# tap_sens.net
KiCad netlist of a schematic drawn in EAGLE
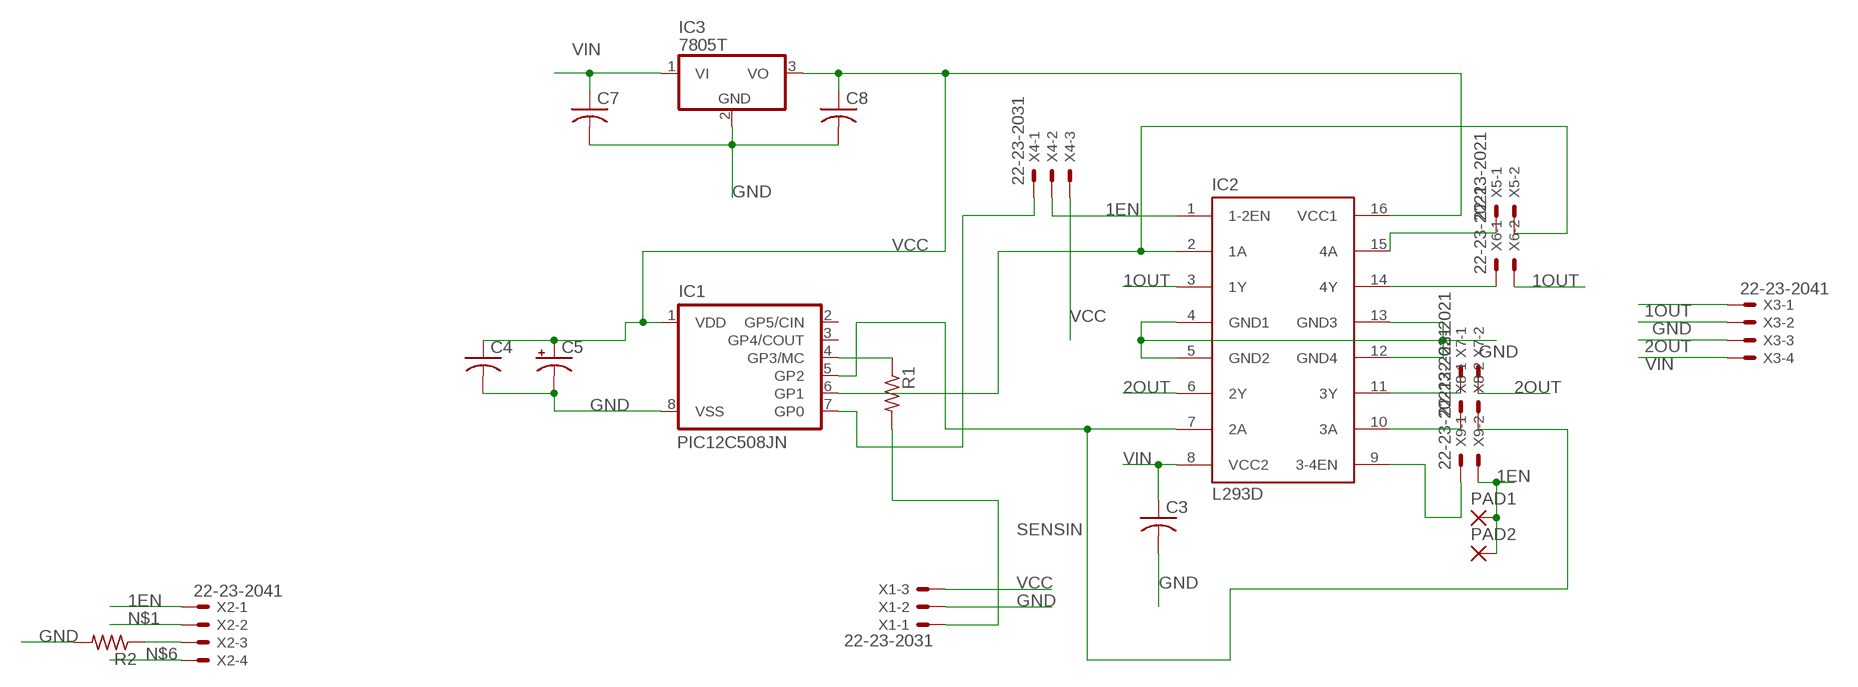
[diagram p0: schematic, sheet 1]

(export (version "E")
  (design (tool "Eeschema 10.0.6"))
  (components
    (comp (ref "C3")
      (value "C-US050-025X075")
      (footprint "eagle-import:C050-025X075")
      (libsource (lib "eagle-import") (part "C-US050-025X075"))
    )
    (comp (ref "C4")
      (value "C-US050-025X075")
      (footprint "eagle-import:C050-025X075")
      (libsource (lib "eagle-import") (part "C-US050-025X075"))
    )
    (comp (ref "C5")
      (value "CPOL-USE5-8.5")
      (footprint "eagle-import:E5-8,5")
      (libsource (lib "eagle-import") (part "CPOL-USE5-8.5"))
    )
    (comp (ref "C7")
      (value "C-US050-025X075")
      (footprint "eagle-import:C050-025X075")
      (libsource (lib "eagle-import") (part "C-US050-025X075"))
    )
    (comp (ref "C8")
      (value "C-US050-025X075")
      (footprint "eagle-import:C050-025X075")
      (libsource (lib "eagle-import") (part "C-US050-025X075"))
    )
    (comp (ref "IC1")
      (value "PIC12C508JN")
      (footprint "eagle-import:DIL8")
      (fields (field (name "MF") "MICROCHIP") (field (name "MPN") "PIC12C508-04/P"))
      (libsource (lib "eagle-import") (part "PIC12C?JN508"))
    )
    (comp (ref "IC2")
      (value "L293D")
      (footprint "eagle-import:DIL16")
      (libsource (lib "eagle-import") (part "L293D"))
    )
    (comp (ref "IC3")
      (value "7805T")
      (footprint "eagle-import:TO220H")
      (libsource (lib "eagle-import") (part "78T05"))
    )
    (comp (ref "PAD1")
      (value "2,54/0,8")
      (footprint "eagle-import:2,54_0,8")
      (libsource (lib "eagle-import") (part "2,54/0,8"))
    )
    (comp (ref "PAD2")
      (value "2,54/0,8")
      (footprint "eagle-import:2,54_0,8")
      (libsource (lib "eagle-import") (part "2,54/0,8"))
    )
    (comp (ref "R1")
      (value "R-US_0207/10")
      (footprint "eagle-import:0207_10")
      (libsource (lib "eagle-import") (part "R-US_0207/10"))
    )
    (comp (ref "R2")
      (value "R-US_0207/10")
      (footprint "eagle-import:0207_10")
      (libsource (lib "eagle-import") (part "R-US_0207/10"))
    )
    (comp (ref "X1")
      (value "22-23-2031")
      (footprint "eagle-import:22-23-2031")
      (fields (field (name "MF") "MOLEX"))
      (libsource (lib "eagle-import") (part "22-23-2031"))
    )
    (comp (ref "X2")
      (value "22-23-2041")
      (footprint "eagle-import:22-23-2041")
      (fields (field (name "MF") "MOLEX"))
      (libsource (lib "eagle-import") (part "22-23-2041"))
    )
    (comp (ref "X3")
      (value "22-23-2041")
      (footprint "eagle-import:22-23-2041")
      (fields (field (name "MF") "MOLEX"))
      (libsource (lib "eagle-import") (part "22-23-2041"))
    )
    (comp (ref "X4")
      (value "22-23-2031")
      (footprint "eagle-import:22-23-2031")
      (fields (field (name "MF") "MOLEX"))
      (libsource (lib "eagle-import") (part "22-23-2031"))
    )
    (comp (ref "X5")
      (value "22-23-2021")
      (footprint "eagle-import:22-23-2021")
      (fields (field (name "MF") "MOLEX"))
      (libsource (lib "eagle-import") (part "22-23-2021"))
    )
    (comp (ref "X6")
      (value "22-23-2021")
      (footprint "eagle-import:22-23-2021")
      (fields (field (name "MF") "MOLEX"))
      (libsource (lib "eagle-import") (part "22-23-2021"))
    )
    (comp (ref "X7")
      (value "22-23-2021")
      (footprint "eagle-import:22-23-2021")
      (fields (field (name "MF") "MOLEX"))
      (libsource (lib "eagle-import") (part "22-23-2021"))
    )
    (comp (ref "X8")
      (value "22-23-2021")
      (footprint "eagle-import:22-23-2021")
      (fields (field (name "MF") "MOLEX"))
      (libsource (lib "eagle-import") (part "22-23-2021"))
    )
    (comp (ref "X9")
      (value "22-23-2021")
      (footprint "eagle-import:22-23-2021")
      (fields (field (name "MF") "MOLEX"))
      (libsource (lib "eagle-import") (part "22-23-2021"))
    )
  )
  (nets
    (net (code "1") (name "/1EN") (class "Default")
      (node (ref "IC2") (pin "1") (pinfunction "1-2EN_1") (pintype "input"))
      (node (ref "PAD1") (pin "1") (pinfunction "P_1") (pintype "passive"))
      (node (ref "PAD2") (pin "1") (pinfunction "P_1") (pintype "passive"))
      (node (ref "X2") (pin "1") (pinfunction "S_1") (pintype "passive"))
      (node (ref "X4") (pin "2") (pinfunction "S_2") (pintype "passive"))
      (node (ref "X9") (pin "2") (pinfunction "S_2") (pintype "passive"))
    )
    (net (code "2") (name "/1OUT") (class "Default")
      (node (ref "IC2") (pin "3") (pinfunction "1Y_3") (pintype "output"))
      (node (ref "X3") (pin "1") (pinfunction "S_1") (pintype "passive"))
      (node (ref "X6") (pin "2") (pinfunction "S_2") (pintype "passive"))
    )
    (net (code "3") (name "/2OUT") (class "Default")
      (node (ref "IC2") (pin "6") (pinfunction "2Y_6") (pintype "output"))
      (node (ref "X3") (pin "3") (pinfunction "S_3") (pintype "passive"))
      (node (ref "X7") (pin "2") (pinfunction "S_2") (pintype "passive"))
    )
    (net (code "4") (name "/GND") (class "Default")
      (node (ref "C3") (pin "2") (pinfunction "2_2") (pintype "passive"))
      (node (ref "C4") (pin "2") (pinfunction "2_2") (pintype "passive"))
      (node (ref "C5") (pin "-") (pinfunction "-_-") (pintype "passive"))
      (node (ref "C7") (pin "2") (pinfunction "2_2") (pintype "passive"))
      (node (ref "C8") (pin "2") (pinfunction "2_2") (pintype "passive"))
      (node (ref "IC1") (pin "8") (pinfunction "VSS_8") (pintype "power_in"))
      (node (ref "IC2") (pin "12") (pinfunction "GND4_12") (pintype "power_in"))
      (node (ref "IC2") (pin "13") (pinfunction "GND3_13") (pintype "power_in"))
      (node (ref "IC2") (pin "4") (pinfunction "GND1_4") (pintype "power_in"))
      (node (ref "IC2") (pin "5") (pinfunction "GND2_5") (pintype "power_in"))
      (node (ref "IC3") (pin "2") (pinfunction "GND_2") (pintype "passive"))
      (node (ref "R2") (pin "2") (pinfunction "2_2") (pintype "passive"))
      (node (ref "X1") (pin "2") (pinfunction "S_2") (pintype "passive"))
      (node (ref "X3") (pin "2") (pinfunction "S_2") (pintype "passive"))
    )
    (net (code "5") (name "/N$1") (class "Default")
      (node (ref "IC1") (pin "6") (pinfunction "GP1_6") (pintype "bidirectional"))
      (node (ref "IC2") (pin "2") (pinfunction "1A_2") (pintype "input"))
      (node (ref "X2") (pin "2") (pinfunction "S_2") (pintype "passive"))
      (node (ref "X5") (pin "2") (pinfunction "S_2") (pintype "passive"))
    )
    (net (code "6") (name "/N$6") (class "Default")
      (node (ref "IC1") (pin "5") (pinfunction "GP2_5") (pintype "bidirectional"))
      (node (ref "IC2") (pin "7") (pinfunction "2A_7") (pintype "input"))
      (node (ref "X2") (pin "4") (pinfunction "S_4") (pintype "passive"))
      (node (ref "X8") (pin "2") (pinfunction "S_2") (pintype "passive"))
    )
    (net (code "7") (name "/SENSIN") (class "Default")
      (node (ref "R1") (pin "2") (pinfunction "2_2") (pintype "passive"))
      (node (ref "X1") (pin "1") (pinfunction "S_1") (pintype "passive"))
    )
    (net (code "8") (name "/VCC") (class "Default")
      (node (ref "C4") (pin "1") (pinfunction "1_1") (pintype "passive"))
      (node (ref "C5") (pin "+") (pinfunction "+_+") (pintype "passive"))
      (node (ref "C8") (pin "1") (pinfunction "1_1") (pintype "passive"))
      (node (ref "IC1") (pin "1") (pinfunction "VDD_1") (pintype "power_in"))
      (node (ref "IC2") (pin "16") (pinfunction "VCC1_16") (pintype "power_in"))
      (node (ref "IC3") (pin "3") (pinfunction "VO_3") (pintype "passive"))
      (node (ref "X1") (pin "3") (pinfunction "S_3") (pintype "passive"))
      (node (ref "X4") (pin "3") (pinfunction "S_3") (pintype "passive"))
    )
    (net (code "9") (name "/VIN") (class "Default")
      (node (ref "C3") (pin "1") (pinfunction "1_1") (pintype "passive"))
      (node (ref "C7") (pin "1") (pinfunction "1_1") (pintype "passive"))
      (node (ref "IC2") (pin "8") (pinfunction "VCC2_8") (pintype "power_in"))
      (node (ref "IC3") (pin "1") (pinfunction "VI_1") (pintype "input"))
      (node (ref "X3") (pin "4") (pinfunction "S_4") (pintype "passive"))
    )
    (net (code "10") (name "Net-(IC1-GP0)") (class "Default")
      (node (ref "IC1") (pin "7") (pinfunction "GP0_7") (pintype "bidirectional"))
      (node (ref "X4") (pin "1") (pinfunction "S_1") (pintype "passive"))
    )
    (net (code "11") (name "Net-(IC1-GP3{slash}MC)") (class "Default")
      (node (ref "IC1") (pin "4") (pinfunction "GP3/MC_4") (pintype "input"))
      (node (ref "R1") (pin "1") (pinfunction "1_1") (pintype "passive"))
    )
    (net (code "12") (name "Net-(IC2-3-4EN)") (class "Default")
      (node (ref "IC2") (pin "9") (pinfunction "3-4EN_9") (pintype "input"))
      (node (ref "X9") (pin "1") (pinfunction "S_1") (pintype "passive"))
    )
    (net (code "13") (name "Net-(IC2-3A)") (class "Default")
      (node (ref "IC2") (pin "10") (pinfunction "3A_10") (pintype "input"))
      (node (ref "X8") (pin "1") (pinfunction "S_1") (pintype "passive"))
    )
    (net (code "14") (name "Net-(IC2-3Y)") (class "Default")
      (node (ref "IC2") (pin "11") (pinfunction "3Y_11") (pintype "output"))
      (node (ref "X7") (pin "1") (pinfunction "S_1") (pintype "passive"))
    )
    (net (code "15") (name "Net-(IC2-4A)") (class "Default")
      (node (ref "IC2") (pin "15") (pinfunction "4A_15") (pintype "input"))
      (node (ref "X5") (pin "1") (pinfunction "S_1") (pintype "passive"))
    )
    (net (code "16") (name "Net-(IC2-4Y)") (class "Default")
      (node (ref "IC2") (pin "14") (pinfunction "4Y_14") (pintype "output"))
      (node (ref "X6") (pin "1") (pinfunction "S_1") (pintype "passive"))
    )
    (net (code "17") (name "Net-(X2C-S)") (class "Default")
      (node (ref "R2") (pin "1") (pinfunction "1_1") (pintype "passive"))
      (node (ref "X2") (pin "3") (pinfunction "S_3") (pintype "passive"))
    )
    (net (code "18") (name "unconnected-(IC1-GP4{slash}COUT-Pad3)") (class "Default")
      (node (ref "IC1") (pin "3") (pinfunction "GP4/COUT_3") (pintype "bidirectional"))
    )
    (net (code "19") (name "unconnected-(IC1-GP5{slash}CIN-Pad2)") (class "Default")
      (node (ref "IC1") (pin "2") (pinfunction "GP5/CIN_2") (pintype "bidirectional"))
    )
  )
)
